# LVDS_IFC_DDS.net
KiCad netlist of a schematic drawn in Altium Designer
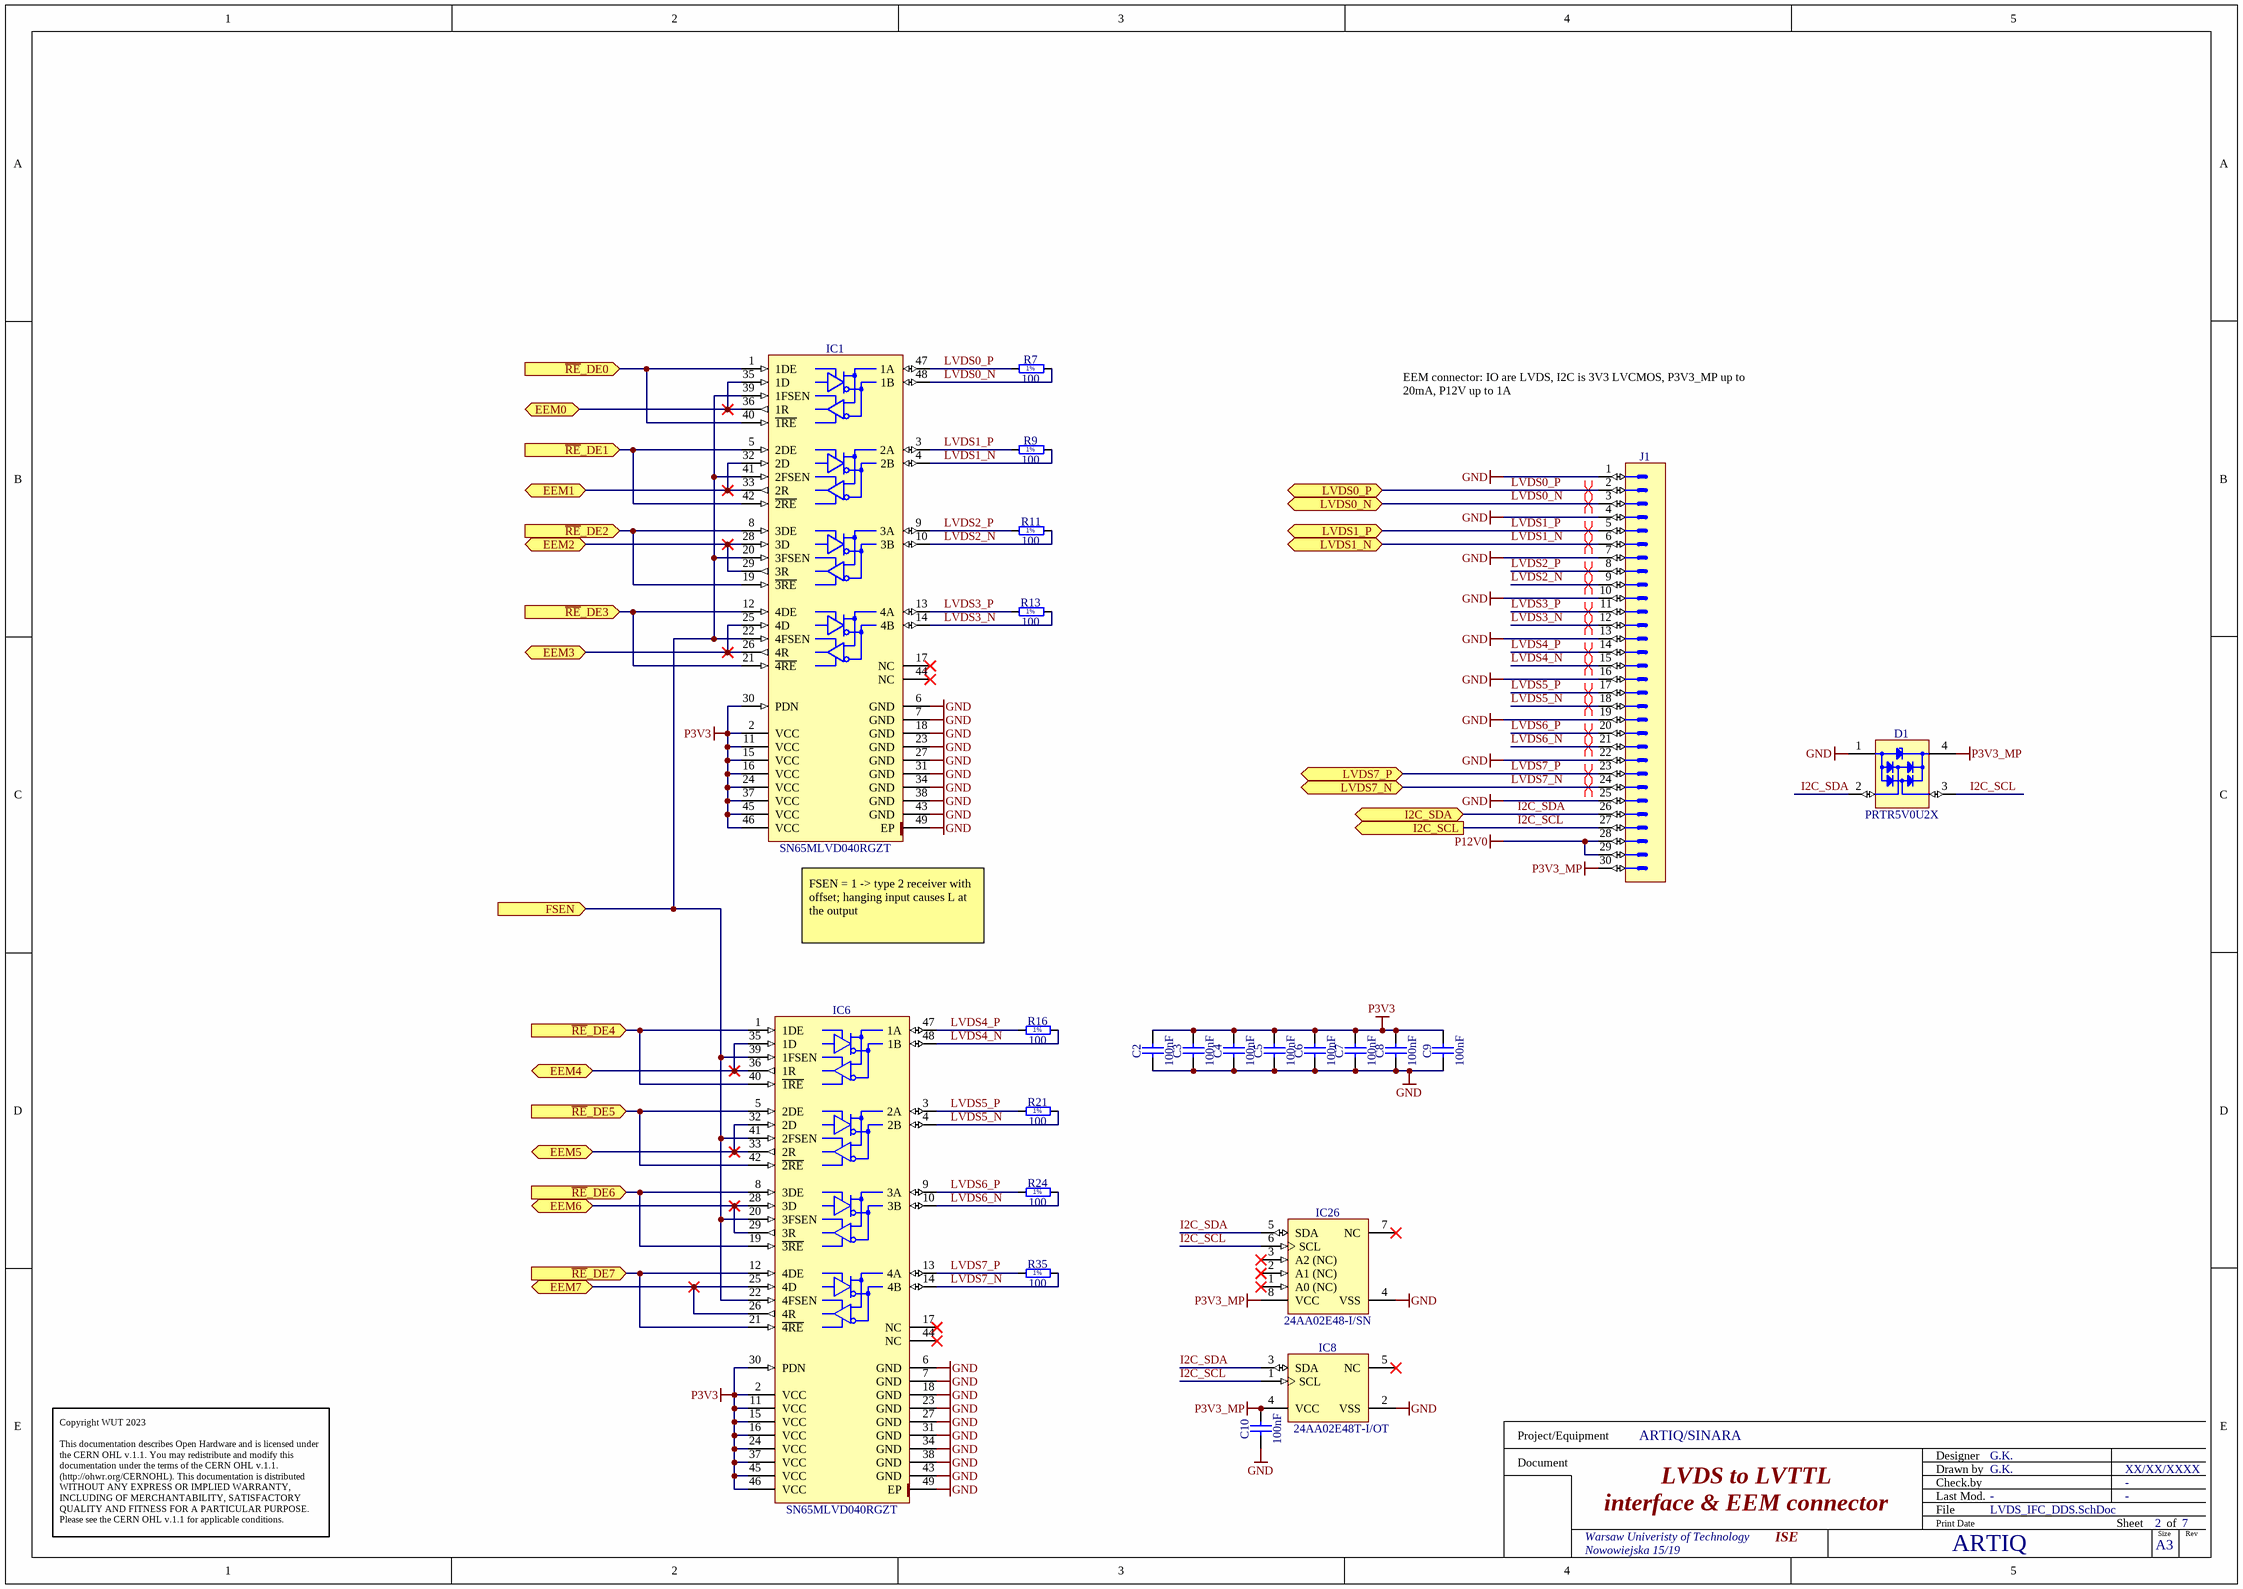
[diagram p0: LVDS_IFC_DDS.SchDoc]

(export (version "E")
  (design (tool "Eeschema 10.0.6"))
  (components
    (comp (ref "C2")
      (value "100nF")
      (footprint "CAPC1005X55N")
      (description "Non-polarised capacitor")
      (fields
        (field (name "PART NUMBER") "CC0402_100NF_16V_10%_X5R")
        (field (name "VOLTAGE") "16V")
        (field (name "AUTHOR") "CERN DEM JLC")
      )
      (libsource (lib "Capacitors") (part "Capacitor - non polarized"))
    )
    (comp (ref "C3")
      (value "100nF")
      (footprint "CAPC1005X55N")
      (description "Non-polarised capacitor")
      (fields
        (field (name "PART NUMBER") "CC0402_100NF_16V_10%_X5R")
        (field (name "VOLTAGE") "16V")
        (field (name "AUTHOR") "CERN DEM JLC")
      )
      (libsource (lib "Capacitors") (part "Capacitor - non polarized"))
    )
    (comp (ref "C4")
      (value "100nF")
      (footprint "CAPC1005X55N")
      (description "Non-polarised capacitor")
      (fields
        (field (name "PART NUMBER") "CC0402_100NF_16V_10%_X5R")
        (field (name "VOLTAGE") "16V")
        (field (name "AUTHOR") "CERN DEM JLC")
      )
      (libsource (lib "Capacitors") (part "Capacitor - non polarized"))
    )
    (comp (ref "C5")
      (value "100nF")
      (footprint "CAPC1005X55N")
      (description "Non-polarised capacitor")
      (fields
        (field (name "PART NUMBER") "CC0402_100NF_16V_10%_X5R")
        (field (name "VOLTAGE") "16V")
        (field (name "AUTHOR") "CERN DEM JLC")
      )
      (libsource (lib "Capacitors") (part "Capacitor - non polarized"))
    )
    (comp (ref "C6")
      (value "100nF")
      (footprint "CAPC1005X55N")
      (description "Non-polarised capacitor")
      (fields
        (field (name "PART NUMBER") "CC0402_100NF_16V_10%_X5R")
        (field (name "VOLTAGE") "16V")
        (field (name "AUTHOR") "CERN DEM JLC")
      )
      (libsource (lib "Capacitors") (part "Capacitor - non polarized"))
    )
    (comp (ref "C7")
      (value "100nF")
      (footprint "CAPC1005X55N")
      (description "Non-polarised capacitor")
      (fields
        (field (name "PART NUMBER") "CC0402_100NF_16V_10%_X5R")
        (field (name "VOLTAGE") "16V")
        (field (name "AUTHOR") "CERN DEM JLC")
      )
      (libsource (lib "Capacitors") (part "Capacitor - non polarized"))
    )
    (comp (ref "C8")
      (value "100nF")
      (footprint "CAPC1005X55N")
      (description "Non-polarised capacitor")
      (fields
        (field (name "PART NUMBER") "CC0402_100NF_16V_10%_X5R")
        (field (name "VOLTAGE") "16V")
        (field (name "AUTHOR") "CERN DEM JLC")
      )
      (libsource (lib "Capacitors") (part "Capacitor - non polarized"))
    )
    (comp (ref "C9")
      (value "100nF")
      (footprint "CAPC1005X55N")
      (description "Non-polarised capacitor")
      (fields
        (field (name "PART NUMBER") "CC0402_100NF_16V_10%_X5R")
        (field (name "VOLTAGE") "16V")
        (field (name "AUTHOR") "CERN DEM JLC")
      )
      (libsource (lib "Capacitors") (part "Capacitor - non polarized"))
    )
    (comp (ref "C10")
      (value "100nF")
      (footprint "CAPC1005X55N")
      (description "Non-polarised capacitor")
      (fields
        (field (name "PART NUMBER") "CC0402_100NF_16V_10%_X5R")
        (field (name "VOLTAGE") "16V")
        (field (name "AUTHOR") "CERN DEM JLC")
      )
      (libsource (lib "Capacitors") (part "Capacitor - non polarized"))
    )
    (comp (ref "D1")
      (value "PRTR5V0U2X")
      (footprint "SOT190P230X110-4N")
      (description "Ultra Low Capacitance Double Rail-to-Rail ESD Protection Diode")
      (fields
        (field (name "VOLTAGE") "5.5V")
        (field (name "MANUFACTURER") "NXP SEMICONDUCTORS")
        (field (name "AUTHOR") "CERN DEM JLC")
      )
      (libsource (lib "ICs And Semiconductors") (part "PRTR5V0U2X"))
    )
    (comp (ref "IC1")
      (value "SN65MLVD040RGZT")
      (footprint "QFN50P700X700X100-49N-S420")
      (description "4-Channel Half-Duplex M-LVDS Line Transceiver")
      (fields (field (name "MANUFACTURER") "TEXAS INSTRUMENTS") (field (name "AUTHOR") "CERN DEM JLC"))
      (libsource (lib "ICs And Semiconductors") (part "SN65MLVD040"))
    )
    (comp (ref "IC6")
      (value "SN65MLVD040RGZT")
      (footprint "QFN50P700X700X100-49N-S420")
      (description "4-Channel Half-Duplex M-LVDS Line Transceiver")
      (fields (field (name "MANUFACTURER") "TEXAS INSTRUMENTS") (field (name "AUTHOR") "CERN DEM JLC"))
      (libsource (lib "ICs And Semiconductors") (part "SN65MLVD040"))
    )
    (comp (ref "IC8")
      (value "24AA02E48T-I/OT")
      (footprint "SOT95P280X145-5N")
      (description "1.7V-5.5V, 2K I2C Serial EEPROM With EUI-48 Node Identity")
      (fields (field (name "MANUFACTURER") "MICROCHIP TECHNOLOGY") (field (name "AUTHOR") "CERN DEM MR"))
      (libsource (lib "ICs And Semiconductors") (part "24AA02E48T-I/OT"))
    )
    (comp (ref "IC26")
      (value "24AA02E48-I/SN")
      (footprint "SOIC127P600X175-8N")
      (description "1.7V-5.5V, 2K I2C™ Serial EEPROMs with EUI-48™ Node Identity")
      (fields (field (name "MANUFACTURER") "MICROCHIP TECHNOLOGY") (field (name "AUTHOR") "CERN DEM MR"))
      (libsource (lib "ICS-logic") (part "MEM_24AA02E48-I/SN"))
    )
    (comp (ref "J1")
      (value "~")
      (footprint "3M_N2530-6002RB")
      (description "Connector 30 Male")
      (fields
        (field (name "PART NUMBER") "3M_N2530-6002RB")
        (field (name "MANUFACTURER") "3M")
        (field (name "AUTHOR") "CERN DEM JLC")
      )
      (libsource (lib "Connectors") (part "Connector 30 Male"))
    )
    (comp (ref "R7")
      (value "100")
      (footprint "RESC1005X40N")
      (description "Resistor - 1%")
      (fields
        (field (name "PART NUMBER") "R0402_100R_1%_0.1W_100PPM")
        (field (name "POWER") "0.1W")
        (field (name "AUTHOR") "CERN DEM JLC")
      )
      (libsource (lib "Resistors") (part "Resistor - 1%"))
    )
    (comp (ref "R9")
      (value "100")
      (footprint "RESC1005X40N")
      (description "Resistor - 1%")
      (fields
        (field (name "PART NUMBER") "R0402_100R_1%_0.1W_100PPM")
        (field (name "POWER") "0.1W")
        (field (name "AUTHOR") "CERN DEM JLC")
      )
      (libsource (lib "Resistors") (part "Resistor - 1%"))
    )
    (comp (ref "R11")
      (value "100")
      (footprint "RESC1005X40N")
      (description "Resistor - 1%")
      (fields
        (field (name "PART NUMBER") "R0402_100R_1%_0.1W_100PPM")
        (field (name "POWER") "0.1W")
        (field (name "AUTHOR") "CERN DEM JLC")
      )
      (libsource (lib "Resistors") (part "Resistor - 1%"))
    )
    (comp (ref "R13")
      (value "100")
      (footprint "RESC1005X40N")
      (description "Resistor - 1%")
      (fields
        (field (name "PART NUMBER") "R0402_100R_1%_0.1W_100PPM")
        (field (name "POWER") "0.1W")
        (field (name "AUTHOR") "CERN DEM JLC")
      )
      (libsource (lib "Resistors") (part "Resistor - 1%"))
    )
    (comp (ref "R16")
      (value "100")
      (footprint "RESC1005X40N")
      (description "Resistor - 1%")
      (fields
        (field (name "PART NUMBER") "R0402_100R_1%_0.1W_100PPM")
        (field (name "POWER") "0.1W")
        (field (name "AUTHOR") "CERN DEM JLC")
      )
      (libsource (lib "Resistors") (part "Resistor - 1%"))
    )
    (comp (ref "R21")
      (value "100")
      (footprint "RESC1005X40N")
      (description "Resistor - 1%")
      (fields
        (field (name "PART NUMBER") "R0402_100R_1%_0.1W_100PPM")
        (field (name "POWER") "0.1W")
        (field (name "AUTHOR") "CERN DEM JLC")
      )
      (libsource (lib "Resistors") (part "Resistor - 1%"))
    )
    (comp (ref "R24")
      (value "100")
      (footprint "RESC1005X40N")
      (description "Resistor - 1%")
      (fields
        (field (name "PART NUMBER") "R0402_100R_1%_0.1W_100PPM")
        (field (name "POWER") "0.1W")
        (field (name "AUTHOR") "CERN DEM JLC")
      )
      (libsource (lib "Resistors") (part "Resistor - 1%"))
    )
    (comp (ref "R35")
      (value "100")
      (footprint "RESC1005X40N")
      (description "Resistor - 1%")
      (fields
        (field (name "PART NUMBER") "R0402_100R_1%_0.1W_100PPM")
        (field (name "POWER") "0.1W")
        (field (name "AUTHOR") "CERN DEM JLC")
      )
      (libsource (lib "Resistors") (part "Resistor - 1%"))
    )
  )
  (nets
    (net (code "1") (name "/EEM0") (class "Default")
      (node (ref "IC1") (pin "35") (pinfunction "1D_35") (pintype "input"))
      (node (ref "IC1") (pin "36") (pinfunction "1R_36") (pintype "output"))
    )
    (net (code "2") (name "/EEM1") (class "Default")
      (node (ref "IC1") (pin "32") (pinfunction "2D_32") (pintype "input"))
      (node (ref "IC1") (pin "33") (pinfunction "2R_33") (pintype "output"))
    )
    (net (code "3") (name "/EEM2") (class "Default")
      (node (ref "IC1") (pin "28") (pinfunction "3D_28") (pintype "input"))
      (node (ref "IC1") (pin "29") (pinfunction "3R_29") (pintype "output"))
    )
    (net (code "4") (name "/EEM3") (class "Default")
      (node (ref "IC1") (pin "25") (pinfunction "4D_25") (pintype "input"))
      (node (ref "IC1") (pin "26") (pinfunction "4R_26") (pintype "output"))
    )
    (net (code "5") (name "/EEM4") (class "Default")
      (node (ref "IC6") (pin "35") (pinfunction "1D_35") (pintype "input"))
      (node (ref "IC6") (pin "36") (pinfunction "1R_36") (pintype "output"))
    )
    (net (code "6") (name "/EEM5") (class "Default")
      (node (ref "IC6") (pin "32") (pinfunction "2D_32") (pintype "input"))
      (node (ref "IC6") (pin "33") (pinfunction "2R_33") (pintype "output"))
    )
    (net (code "7") (name "/EEM6") (class "Default")
      (node (ref "IC6") (pin "28") (pinfunction "3D_28") (pintype "input"))
      (node (ref "IC6") (pin "29") (pinfunction "3R_29") (pintype "output"))
    )
    (net (code "8") (name "/EEM7") (class "Default")
      (node (ref "IC6") (pin "25") (pinfunction "4D_25") (pintype "input"))
      (node (ref "IC6") (pin "26") (pinfunction "4R_26") (pintype "output"))
    )
    (net (code "9") (name "/FSEN") (class "Default")
      (node (ref "IC1") (pin "20") (pinfunction "3FSEN_20") (pintype "input"))
      (node (ref "IC1") (pin "22") (pinfunction "4FSEN_22") (pintype "input"))
      (node (ref "IC1") (pin "39") (pinfunction "1FSEN_39") (pintype "input"))
      (node (ref "IC1") (pin "41") (pinfunction "2FSEN_41") (pintype "input"))
      (node (ref "IC6") (pin "20") (pinfunction "3FSEN_20") (pintype "input"))
      (node (ref "IC6") (pin "22") (pinfunction "4FSEN_22") (pintype "input"))
      (node (ref "IC6") (pin "39") (pinfunction "1FSEN_39") (pintype "input"))
      (node (ref "IC6") (pin "41") (pinfunction "2FSEN_41") (pintype "input"))
    )
    (net (code "10") (name "/I2C_SCL") (class "Default")
      (node (ref "D1") (pin "3") (pinfunction "I/O2_3") (pintype "bidirectional"))
      (node (ref "IC26") (pin "6") (pinfunction "SCL_6") (pintype "input"))
      (node (ref "IC8") (pin "1") (pinfunction "SCL_1") (pintype "input"))
      (node (ref "J1") (pin "27") (pinfunction "27_27") (pintype "bidirectional"))
    )
    (net (code "11") (name "/I2C_SDA") (class "Default")
      (node (ref "D1") (pin "2") (pinfunction "I/O1_2") (pintype "bidirectional"))
      (node (ref "IC26") (pin "5") (pinfunction "SDA_5") (pintype "bidirectional"))
      (node (ref "IC8") (pin "3") (pinfunction "SDA_3") (pintype "bidirectional"))
      (node (ref "J1") (pin "26") (pinfunction "26_26") (pintype "bidirectional"))
    )
    (net (code "12") (name "/LVDS0_N") (class "Default")
      (node (ref "IC1") (pin "48") (pinfunction "1B_48") (pintype "bidirectional"))
      (node (ref "J1") (pin "3") (pinfunction "3_3") (pintype "bidirectional"))
      (node (ref "R7") (pin "2") (pinfunction "2_2") (pintype "passive"))
    )
    (net (code "13") (name "/LVDS0_P") (class "Default")
      (node (ref "IC1") (pin "47") (pinfunction "1A_47") (pintype "bidirectional"))
      (node (ref "J1") (pin "2") (pinfunction "2_2") (pintype "bidirectional"))
      (node (ref "R7") (pin "1") (pinfunction "1_1") (pintype "passive"))
    )
    (net (code "14") (name "/LVDS1_N") (class "Default")
      (node (ref "IC1") (pin "4") (pinfunction "2B_4") (pintype "bidirectional"))
      (node (ref "J1") (pin "6") (pinfunction "6_6") (pintype "bidirectional"))
      (node (ref "R9") (pin "2") (pinfunction "2_2") (pintype "passive"))
    )
    (net (code "15") (name "/LVDS1_P") (class "Default")
      (node (ref "IC1") (pin "3") (pinfunction "2A_3") (pintype "bidirectional"))
      (node (ref "J1") (pin "5") (pinfunction "5_5") (pintype "bidirectional"))
      (node (ref "R9") (pin "1") (pinfunction "1_1") (pintype "passive"))
    )
    (net (code "16") (name "/LVDS2_N") (class "Default")
      (node (ref "IC1") (pin "10") (pinfunction "3B_10") (pintype "bidirectional"))
      (node (ref "J1") (pin "9") (pinfunction "9_9") (pintype "bidirectional"))
      (node (ref "R11") (pin "2") (pinfunction "2_2") (pintype "passive"))
    )
    (net (code "17") (name "/LVDS2_P") (class "Default")
      (node (ref "IC1") (pin "9") (pinfunction "3A_9") (pintype "bidirectional"))
      (node (ref "J1") (pin "8") (pinfunction "8_8") (pintype "bidirectional"))
      (node (ref "R11") (pin "1") (pinfunction "1_1") (pintype "passive"))
    )
    (net (code "18") (name "/LVDS3_N") (class "Default")
      (node (ref "IC1") (pin "14") (pinfunction "4B_14") (pintype "bidirectional"))
      (node (ref "J1") (pin "12") (pinfunction "12_12") (pintype "bidirectional"))
      (node (ref "R13") (pin "2") (pinfunction "2_2") (pintype "passive"))
    )
    (net (code "19") (name "/LVDS3_P") (class "Default")
      (node (ref "IC1") (pin "13") (pinfunction "4A_13") (pintype "bidirectional"))
      (node (ref "J1") (pin "11") (pinfunction "11_11") (pintype "bidirectional"))
      (node (ref "R13") (pin "1") (pinfunction "1_1") (pintype "passive"))
    )
    (net (code "20") (name "/LVDS4_N") (class "Default")
      (node (ref "IC6") (pin "48") (pinfunction "1B_48") (pintype "bidirectional"))
      (node (ref "J1") (pin "15") (pinfunction "15_15") (pintype "bidirectional"))
      (node (ref "R16") (pin "2") (pinfunction "2_2") (pintype "passive"))
    )
    (net (code "21") (name "/LVDS4_P") (class "Default")
      (node (ref "IC6") (pin "47") (pinfunction "1A_47") (pintype "bidirectional"))
      (node (ref "J1") (pin "14") (pinfunction "14_14") (pintype "bidirectional"))
      (node (ref "R16") (pin "1") (pinfunction "1_1") (pintype "passive"))
    )
    (net (code "22") (name "/LVDS5_N") (class "Default")
      (node (ref "IC6") (pin "4") (pinfunction "2B_4") (pintype "bidirectional"))
      (node (ref "J1") (pin "18") (pinfunction "18_18") (pintype "bidirectional"))
      (node (ref "R21") (pin "2") (pinfunction "2_2") (pintype "passive"))
    )
    (net (code "23") (name "/LVDS5_P") (class "Default")
      (node (ref "IC6") (pin "3") (pinfunction "2A_3") (pintype "bidirectional"))
      (node (ref "J1") (pin "17") (pinfunction "17_17") (pintype "bidirectional"))
      (node (ref "R21") (pin "1") (pinfunction "1_1") (pintype "passive"))
    )
    (net (code "24") (name "/LVDS6_N") (class "Default")
      (node (ref "IC6") (pin "10") (pinfunction "3B_10") (pintype "bidirectional"))
      (node (ref "J1") (pin "21") (pinfunction "21_21") (pintype "bidirectional"))
      (node (ref "R24") (pin "2") (pinfunction "2_2") (pintype "passive"))
    )
    (net (code "25") (name "/LVDS6_P") (class "Default")
      (node (ref "IC6") (pin "9") (pinfunction "3A_9") (pintype "bidirectional"))
      (node (ref "J1") (pin "20") (pinfunction "20_20") (pintype "bidirectional"))
      (node (ref "R24") (pin "1") (pinfunction "1_1") (pintype "passive"))
    )
    (net (code "26") (name "/LVDS7_N") (class "Default")
      (node (ref "IC6") (pin "14") (pinfunction "4B_14") (pintype "bidirectional"))
      (node (ref "J1") (pin "24") (pinfunction "24_24") (pintype "bidirectional"))
      (node (ref "R35") (pin "2") (pinfunction "2_2") (pintype "passive"))
    )
    (net (code "27") (name "/LVDS7_P") (class "Default")
      (node (ref "IC6") (pin "13") (pinfunction "4A_13") (pintype "bidirectional"))
      (node (ref "J1") (pin "23") (pinfunction "23_23") (pintype "bidirectional"))
      (node (ref "R35") (pin "1") (pinfunction "1_1") (pintype "passive"))
    )
    (net (code "28") (name "/~{RE}_DE0") (class "Default")
      (node (ref "IC1") (pin "1") (pinfunction "1DE_1") (pintype "input"))
      (node (ref "IC1") (pin "40") (pinfunction "~{1RE}_40") (pintype "input"))
    )
    (net (code "29") (name "/~{RE}_DE1") (class "Default")
      (node (ref "IC1") (pin "42") (pinfunction "~{2RE}_42") (pintype "input"))
      (node (ref "IC1") (pin "5") (pinfunction "2DE_5") (pintype "input"))
    )
    (net (code "30") (name "/~{RE}_DE2") (class "Default")
      (node (ref "IC1") (pin "19") (pinfunction "~{3RE}_19") (pintype "input"))
      (node (ref "IC1") (pin "8") (pinfunction "3DE_8") (pintype "input"))
    )
    (net (code "31") (name "/~{RE}_DE3") (class "Default")
      (node (ref "IC1") (pin "12") (pinfunction "4DE_12") (pintype "input"))
      (node (ref "IC1") (pin "21") (pinfunction "~{4RE}_21") (pintype "input"))
    )
    (net (code "32") (name "/~{RE}_DE4") (class "Default")
      (node (ref "IC6") (pin "1") (pinfunction "1DE_1") (pintype "input"))
      (node (ref "IC6") (pin "40") (pinfunction "~{1RE}_40") (pintype "input"))
    )
    (net (code "33") (name "/~{RE}_DE5") (class "Default")
      (node (ref "IC6") (pin "42") (pinfunction "~{2RE}_42") (pintype "input"))
      (node (ref "IC6") (pin "5") (pinfunction "2DE_5") (pintype "input"))
    )
    (net (code "34") (name "/~{RE}_DE6") (class "Default")
      (node (ref "IC6") (pin "19") (pinfunction "~{3RE}_19") (pintype "input"))
      (node (ref "IC6") (pin "8") (pinfunction "3DE_8") (pintype "input"))
    )
    (net (code "35") (name "/~{RE}_DE7") (class "Default")
      (node (ref "IC6") (pin "12") (pinfunction "4DE_12") (pintype "input"))
      (node (ref "IC6") (pin "21") (pinfunction "~{4RE}_21") (pintype "input"))
    )
    (net (code "36") (name "GND") (class "Default")
      (node (ref "C10") (pin "1") (pinfunction "1_1") (pintype "passive"))
      (node (ref "C2") (pin "1") (pinfunction "1_1") (pintype "passive"))
      (node (ref "C3") (pin "1") (pinfunction "1_1") (pintype "passive"))
      (node (ref "C4") (pin "1") (pinfunction "1_1") (pintype "passive"))
      (node (ref "C5") (pin "1") (pinfunction "1_1") (pintype "passive"))
      (node (ref "C6") (pin "1") (pinfunction "1_1") (pintype "passive"))
      (node (ref "C7") (pin "1") (pinfunction "1_1") (pintype "passive"))
      (node (ref "C8") (pin "1") (pinfunction "1_1") (pintype "passive"))
      (node (ref "C9") (pin "1") (pinfunction "1_1") (pintype "passive"))
      (node (ref "D1") (pin "1") (pinfunction "GND_1") (pintype "power_in"))
      (node (ref "IC1") (pin "18") (pinfunction "GND_18") (pintype "power_in"))
      (node (ref "IC1") (pin "23") (pinfunction "GND_23") (pintype "power_in"))
      (node (ref "IC1") (pin "27") (pinfunction "GND_27") (pintype "power_in"))
      (node (ref "IC1") (pin "31") (pinfunction "GND_31") (pintype "power_in"))
      (node (ref "IC1") (pin "34") (pinfunction "GND_34") (pintype "power_in"))
      (node (ref "IC1") (pin "38") (pinfunction "GND_38") (pintype "power_in"))
      (node (ref "IC1") (pin "43") (pinfunction "GND_43") (pintype "power_in"))
      (node (ref "IC1") (pin "49") (pinfunction "EP_49") (pintype "power_in"))
      (node (ref "IC1") (pin "6") (pinfunction "GND_6") (pintype "power_in"))
      (node (ref "IC1") (pin "7") (pinfunction "GND_7") (pintype "power_in"))
      (node (ref "IC26") (pin "4") (pinfunction "VSS_4") (pintype "power_in"))
      (node (ref "IC6") (pin "18") (pinfunction "GND_18") (pintype "power_in"))
      (node (ref "IC6") (pin "23") (pinfunction "GND_23") (pintype "power_in"))
      (node (ref "IC6") (pin "27") (pinfunction "GND_27") (pintype "power_in"))
      (node (ref "IC6") (pin "31") (pinfunction "GND_31") (pintype "power_in"))
      (node (ref "IC6") (pin "34") (pinfunction "GND_34") (pintype "power_in"))
      (node (ref "IC6") (pin "38") (pinfunction "GND_38") (pintype "power_in"))
      (node (ref "IC6") (pin "43") (pinfunction "GND_43") (pintype "power_in"))
      (node (ref "IC6") (pin "49") (pinfunction "EP_49") (pintype "power_in"))
      (node (ref "IC6") (pin "6") (pinfunction "GND_6") (pintype "power_in"))
      (node (ref "IC6") (pin "7") (pinfunction "GND_7") (pintype "power_in"))
      (node (ref "IC8") (pin "2") (pinfunction "VSS_2") (pintype "power_in"))
      (node (ref "J1") (pin "1") (pinfunction "1_1") (pintype "bidirectional"))
      (node (ref "J1") (pin "10") (pinfunction "10_10") (pintype "bidirectional"))
      (node (ref "J1") (pin "13") (pinfunction "13_13") (pintype "bidirectional"))
      (node (ref "J1") (pin "16") (pinfunction "16_16") (pintype "bidirectional"))
      (node (ref "J1") (pin "19") (pinfunction "19_19") (pintype "bidirectional"))
      (node (ref "J1") (pin "22") (pinfunction "22_22") (pintype "bidirectional"))
      (node (ref "J1") (pin "25") (pinfunction "25_25") (pintype "bidirectional"))
      (node (ref "J1") (pin "4") (pinfunction "4_4") (pintype "bidirectional"))
      (node (ref "J1") (pin "7") (pinfunction "7_7") (pintype "bidirectional"))
    )
    (net (code "37") (name "P3V3") (class "Default")
      (node (ref "C2") (pin "2") (pinfunction "2_2") (pintype "passive"))
      (node (ref "C3") (pin "2") (pinfunction "2_2") (pintype "passive"))
      (node (ref "C4") (pin "2") (pinfunction "2_2") (pintype "passive"))
      (node (ref "C5") (pin "2") (pinfunction "2_2") (pintype "passive"))
      (node (ref "C6") (pin "2") (pinfunction "2_2") (pintype "passive"))
      (node (ref "C7") (pin "2") (pinfunction "2_2") (pintype "passive"))
      (node (ref "C8") (pin "2") (pinfunction "2_2") (pintype "passive"))
      (node (ref "C9") (pin "2") (pinfunction "2_2") (pintype "passive"))
      (node (ref "IC1") (pin "11") (pinfunction "VCC_11") (pintype "power_in"))
      (node (ref "IC1") (pin "15") (pinfunction "VCC_15") (pintype "power_in"))
      (node (ref "IC1") (pin "16") (pinfunction "VCC_16") (pintype "power_in"))
      (node (ref "IC1") (pin "2") (pinfunction "VCC_2") (pintype "power_in"))
      (node (ref "IC1") (pin "24") (pinfunction "VCC_24") (pintype "power_in"))
      (node (ref "IC1") (pin "30") (pinfunction "PDN_30") (pintype "input"))
      (node (ref "IC1") (pin "37") (pinfunction "VCC_37") (pintype "power_in"))
      (node (ref "IC1") (pin "45") (pinfunction "VCC_45") (pintype "power_in"))
      (node (ref "IC1") (pin "46") (pinfunction "VCC_46") (pintype "power_in"))
      (node (ref "IC6") (pin "11") (pinfunction "VCC_11") (pintype "power_in"))
      (node (ref "IC6") (pin "15") (pinfunction "VCC_15") (pintype "power_in"))
      (node (ref "IC6") (pin "16") (pinfunction "VCC_16") (pintype "power_in"))
      (node (ref "IC6") (pin "2") (pinfunction "VCC_2") (pintype "power_in"))
      (node (ref "IC6") (pin "24") (pinfunction "VCC_24") (pintype "power_in"))
      (node (ref "IC6") (pin "30") (pinfunction "PDN_30") (pintype "input"))
      (node (ref "IC6") (pin "37") (pinfunction "VCC_37") (pintype "power_in"))
      (node (ref "IC6") (pin "45") (pinfunction "VCC_45") (pintype "power_in"))
      (node (ref "IC6") (pin "46") (pinfunction "VCC_46") (pintype "power_in"))
    )
    (net (code "38") (name "P3V3_MP") (class "Default")
      (node (ref "C10") (pin "2") (pinfunction "2_2") (pintype "passive"))
      (node (ref "D1") (pin "4") (pinfunction "VCC_4") (pintype "power_in"))
      (node (ref "IC26") (pin "8") (pinfunction "VCC_8") (pintype "power_in"))
      (node (ref "IC8") (pin "4") (pinfunction "VCC_4") (pintype "power_in"))
      (node (ref "J1") (pin "30") (pinfunction "30_30") (pintype "bidirectional"))
    )
    (net (code "39") (name "P12V0") (class "Default")
      (node (ref "J1") (pin "28") (pinfunction "28_28") (pintype "bidirectional"))
      (node (ref "J1") (pin "29") (pinfunction "29_29") (pintype "bidirectional"))
    )
    (net (code "40") (name "unconnected-(IC1-NC-Pad17)") (class "Default")
      (node (ref "IC1") (pin "17") (pinfunction "NC_17") (pintype "passive+no_connect"))
    )
    (net (code "41") (name "unconnected-(IC1-NC-Pad44)") (class "Default")
      (node (ref "IC1") (pin "44") (pinfunction "NC_44") (pintype "passive+no_connect"))
    )
    (net (code "42") (name "unconnected-(IC6-NC-Pad17)") (class "Default")
      (node (ref "IC6") (pin "17") (pinfunction "NC_17") (pintype "passive+no_connect"))
    )
    (net (code "43") (name "unconnected-(IC6-NC-Pad44)") (class "Default")
      (node (ref "IC6") (pin "44") (pinfunction "NC_44") (pintype "passive+no_connect"))
    )
    (net (code "44") (name "unconnected-(IC8-NC-Pad5)") (class "Default")
      (node (ref "IC8") (pin "5") (pinfunction "NC_5") (pintype "passive+no_connect"))
    )
    (net (code "45") (name "unconnected-(IC26-A0_(NC)-Pad1)") (class "Default")
      (node (ref "IC26") (pin "1") (pinfunction "A0_(NC)_1") (pintype "input+no_connect"))
    )
    (net (code "46") (name "unconnected-(IC26-A1_(NC)-Pad2)") (class "Default")
      (node (ref "IC26") (pin "2") (pinfunction "A1_(NC)_2") (pintype "input+no_connect"))
    )
    (net (code "47") (name "unconnected-(IC26-A2_(NC)-Pad3)") (class "Default")
      (node (ref "IC26") (pin "3") (pinfunction "A2_(NC)_3") (pintype "input+no_connect"))
    )
    (net (code "48") (name "unconnected-(IC26-NC-Pad7)") (class "Default")
      (node (ref "IC26") (pin "7") (pinfunction "NC_7") (pintype "passive+no_connect"))
    )
  )
)
